# xbeeBoard.net
KiCad netlist of a schematic drawn in EAGLE
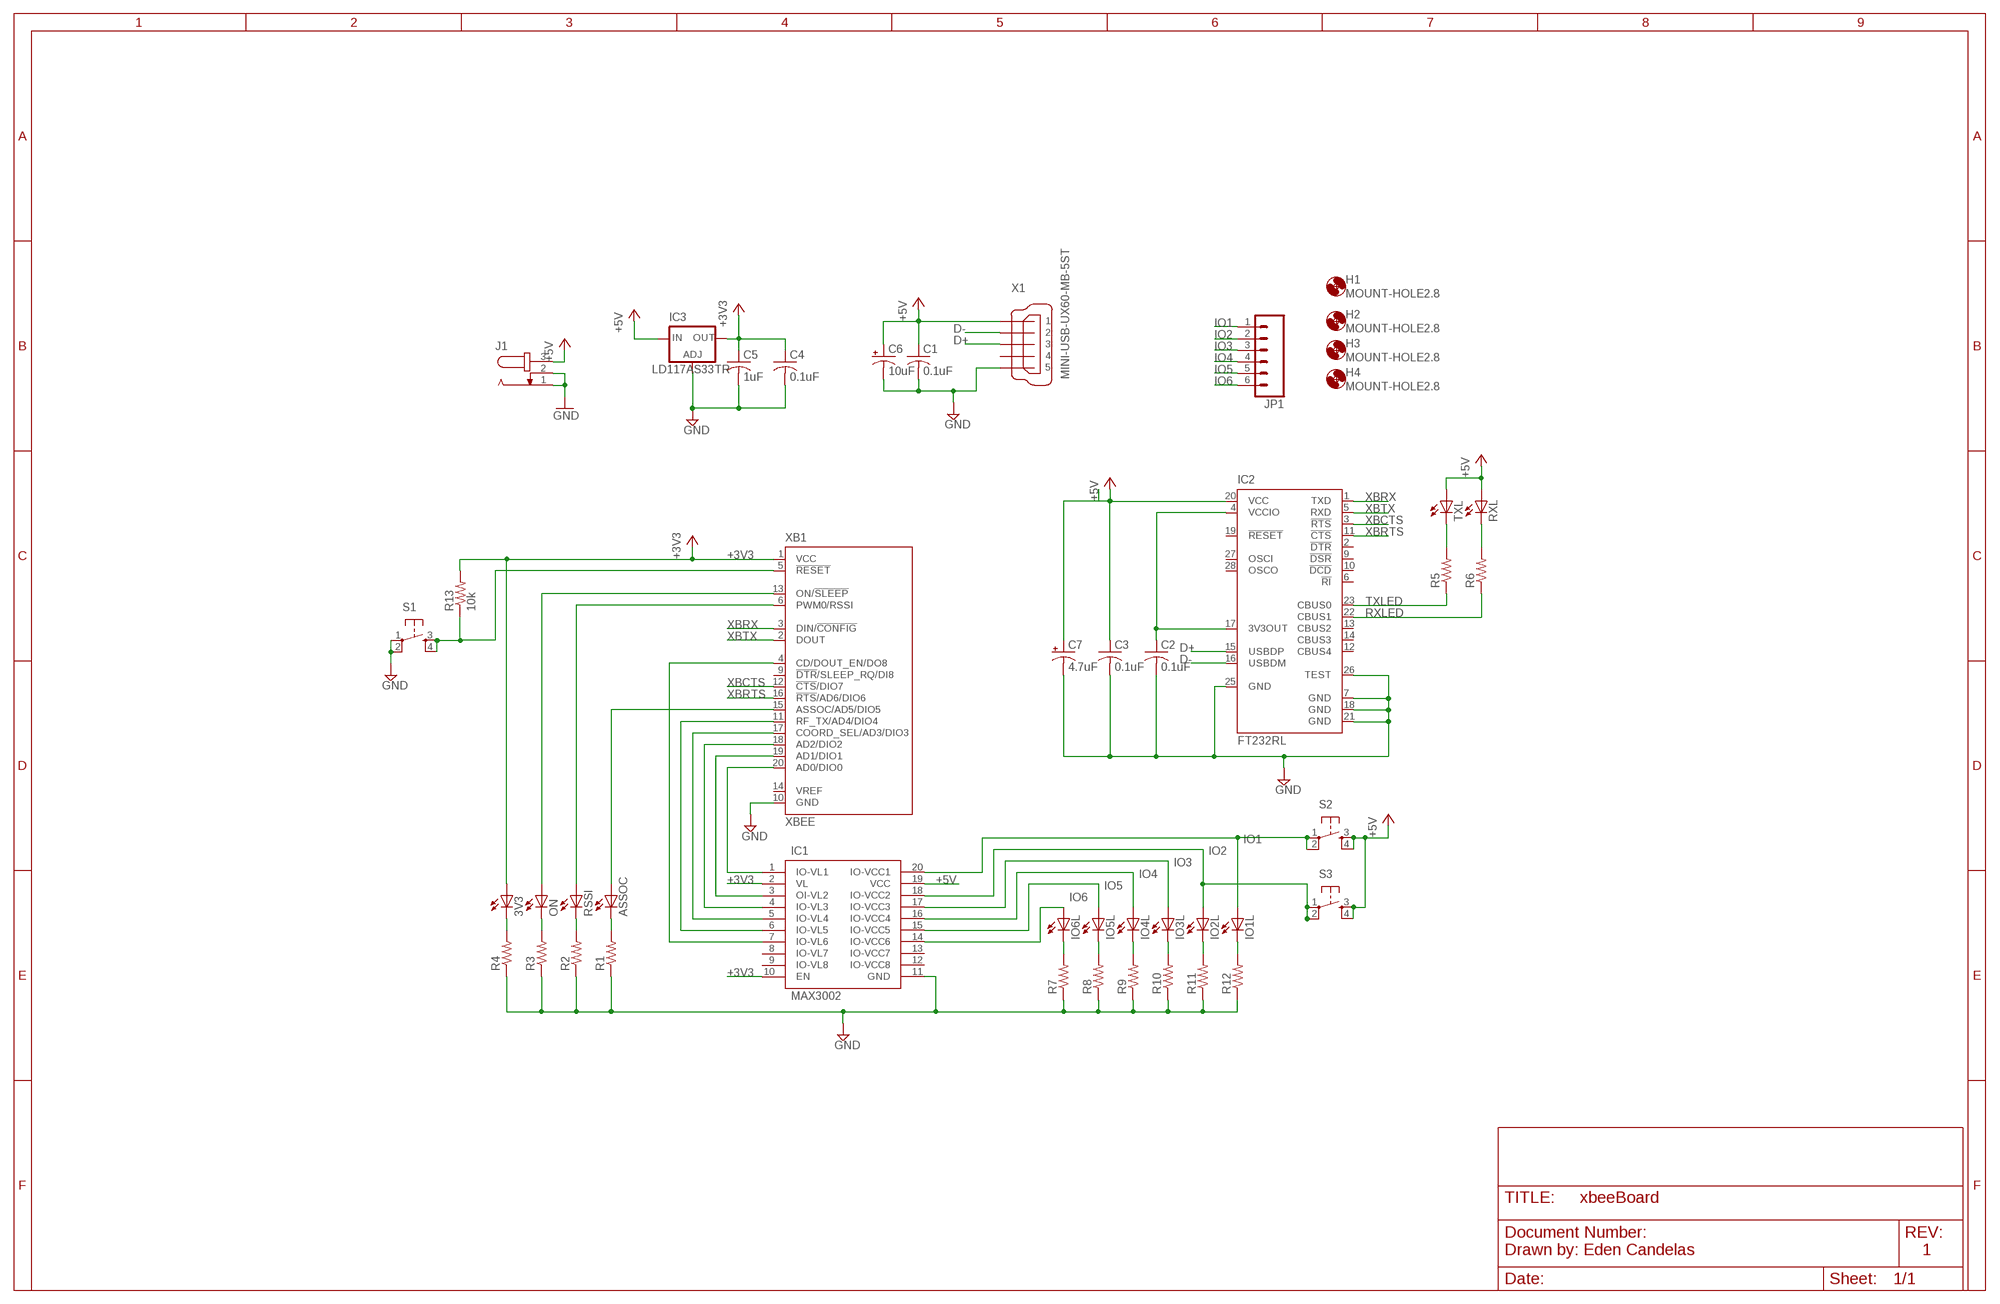
[diagram p0: schematic, sheet 1]

(export (version "E")
  (design (tool "Eeschema 10.0.6"))
  (components
    (comp (ref "3V3")
      (value "LEDCHIPLED_1206")
      (footprint "eagle-import:CHIPLED_1206")
      (libsource (lib "eagle-import") (part "LEDCHIPLED_1206"))
    )
    (comp (ref "ASSOC")
      (value "LEDCHIPLED_1206")
      (footprint "eagle-import:CHIPLED_1206")
      (libsource (lib "eagle-import") (part "LEDCHIPLED_1206"))
    )
    (comp (ref "C1")
      (value "0.1uF")
      (footprint "eagle-import:C1206K")
      (libsource (lib "eagle-import") (part "C-USC1206K"))
    )
    (comp (ref "C2")
      (value "0.1uF")
      (footprint "eagle-import:C1206K")
      (libsource (lib "eagle-import") (part "C-USC1206K"))
    )
    (comp (ref "C3")
      (value "0.1uF")
      (footprint "eagle-import:C1206K")
      (libsource (lib "eagle-import") (part "C-USC1206K"))
    )
    (comp (ref "C4")
      (value "0.1uF")
      (footprint "eagle-import:C1206K")
      (libsource (lib "eagle-import") (part "C-USC1206K"))
    )
    (comp (ref "C5")
      (value "1uF")
      (footprint "eagle-import:C1206K")
      (libsource (lib "eagle-import") (part "C-USC1206K"))
    )
    (comp (ref "C6")
      (value "10uF")
      (footprint "eagle-import:EIA3216")
      (libsource (lib "eagle-import") (part "CAP_POL1206"))
    )
    (comp (ref "C7")
      (value "4.7uF")
      (footprint "eagle-import:EIA3216")
      (libsource (lib "eagle-import") (part "CAP_POL1206"))
    )
    (comp (ref "H1")
      (value "MOUNT-HOLE2.8")
      (footprint "eagle-import:2,8")
      (libsource (lib "eagle-import") (part "MOUNT-HOLE2.8"))
    )
    (comp (ref "H2")
      (value "MOUNT-HOLE2.8")
      (footprint "eagle-import:2,8")
      (libsource (lib "eagle-import") (part "MOUNT-HOLE2.8"))
    )
    (comp (ref "H3")
      (value "MOUNT-HOLE2.8")
      (footprint "eagle-import:2,8")
      (libsource (lib "eagle-import") (part "MOUNT-HOLE2.8"))
    )
    (comp (ref "H4")
      (value "MOUNT-HOLE2.8")
      (footprint "eagle-import:2,8")
      (libsource (lib "eagle-import") (part "MOUNT-HOLE2.8"))
    )
    (comp (ref "IC1")
      (value "MAX3002")
      (footprint "eagle-import:TSSOP-20")
      (libsource (lib "eagle-import") (part "MAX3002"))
    )
    (comp (ref "IC2")
      (value "FT232RL")
      (footprint "eagle-import:SSOP28")
      (libsource (lib "eagle-import") (part "FT232RL"))
    )
    (comp (ref "IC3")
      (value "LD117AS33TR")
      (footprint "eagle-import:SOT223")
      (libsource (lib "eagle-import") (part "LD117A?S33TR"))
    )
    (comp (ref "IO1L")
      (value "LEDCHIPLED_1206")
      (footprint "eagle-import:CHIPLED_1206")
      (libsource (lib "eagle-import") (part "LEDCHIPLED_1206"))
    )
    (comp (ref "IO2L")
      (value "LEDCHIPLED_1206")
      (footprint "eagle-import:CHIPLED_1206")
      (libsource (lib "eagle-import") (part "LEDCHIPLED_1206"))
    )
    (comp (ref "IO3L")
      (value "LEDCHIPLED_1206")
      (footprint "eagle-import:CHIPLED_1206")
      (libsource (lib "eagle-import") (part "LEDCHIPLED_1206"))
    )
    (comp (ref "IO4L")
      (value "LEDCHIPLED_1206")
      (footprint "eagle-import:CHIPLED_1206")
      (libsource (lib "eagle-import") (part "LEDCHIPLED_1206"))
    )
    (comp (ref "IO5L")
      (value "LEDCHIPLED_1206")
      (footprint "eagle-import:CHIPLED_1206")
      (libsource (lib "eagle-import") (part "LEDCHIPLED_1206"))
    )
    (comp (ref "IO6L")
      (value "LEDCHIPLED_1206")
      (footprint "eagle-import:CHIPLED_1206")
      (libsource (lib "eagle-import") (part "LEDCHIPLED_1206"))
    )
    (comp (ref "J1")
      (value "JACK-PLUG0")
      (footprint "eagle-import:SPC4077")
      (libsource (lib "eagle-import") (part "JACK-PLUG0"))
    )
    (comp (ref "JP1")
      (value "M06LONGPADS")
      (footprint "eagle-import:1X06_LONGPADS")
      (libsource (lib "eagle-import") (part "M06LONGPADS"))
    )
    (comp (ref "ON")
      (value "LEDCHIPLED_1206")
      (footprint "eagle-import:CHIPLED_1206")
      (libsource (lib "eagle-import") (part "LEDCHIPLED_1206"))
    )
    (comp (ref "R1")
      (value "R-US_R1206")
      (footprint "eagle-import:R1206")
      (libsource (lib "eagle-import") (part "R-US_R1206"))
    )
    (comp (ref "R2")
      (value "R-US_R1206")
      (footprint "eagle-import:R1206")
      (libsource (lib "eagle-import") (part "R-US_R1206"))
    )
    (comp (ref "R3")
      (value "R-US_R1206")
      (footprint "eagle-import:R1206")
      (libsource (lib "eagle-import") (part "R-US_R1206"))
    )
    (comp (ref "R4")
      (value "R-US_R1206")
      (footprint "eagle-import:R1206")
      (libsource (lib "eagle-import") (part "R-US_R1206"))
    )
    (comp (ref "R5")
      (value "R-US_R1206")
      (footprint "eagle-import:R1206")
      (libsource (lib "eagle-import") (part "R-US_R1206"))
    )
    (comp (ref "R6")
      (value "R-US_R1206")
      (footprint "eagle-import:R1206")
      (libsource (lib "eagle-import") (part "R-US_R1206"))
    )
    (comp (ref "R7")
      (value "R-US_R1206")
      (footprint "eagle-import:R1206")
      (libsource (lib "eagle-import") (part "R-US_R1206"))
    )
    (comp (ref "R8")
      (value "R-US_R1206")
      (footprint "eagle-import:R1206")
      (libsource (lib "eagle-import") (part "R-US_R1206"))
    )
    (comp (ref "R9")
      (value "R-US_R1206")
      (footprint "eagle-import:R1206")
      (libsource (lib "eagle-import") (part "R-US_R1206"))
    )
    (comp (ref "R10")
      (value "R-US_R1206")
      (footprint "eagle-import:R1206")
      (libsource (lib "eagle-import") (part "R-US_R1206"))
    )
    (comp (ref "R11")
      (value "R-US_R1206")
      (footprint "eagle-import:R1206")
      (libsource (lib "eagle-import") (part "R-US_R1206"))
    )
    (comp (ref "R12")
      (value "R-US_R1206")
      (footprint "eagle-import:R1206")
      (libsource (lib "eagle-import") (part "R-US_R1206"))
    )
    (comp (ref "R13")
      (value "10k")
      (footprint "eagle-import:R1206")
      (libsource (lib "eagle-import") (part "R-US_R1206"))
    )
    (comp (ref "RSSI")
      (value "LEDCHIPLED_1206")
      (footprint "eagle-import:CHIPLED_1206")
      (libsource (lib "eagle-import") (part "LEDCHIPLED_1206"))
    )
    (comp (ref "RXL")
      (value "LEDCHIPLED_1206")
      (footprint "eagle-import:CHIPLED_1206")
      (libsource (lib "eagle-import") (part "LEDCHIPLED_1206"))
    )
    (comp (ref "S1")
      (value "TAC_SWITCHPTH")
      (footprint "eagle-import:TACTILE-PTH")
      (libsource (lib "eagle-import") (part "TAC_SWITCHPTH"))
    )
    (comp (ref "S2")
      (value "TAC_SWITCHPTH")
      (footprint "eagle-import:TACTILE-PTH")
      (libsource (lib "eagle-import") (part "TAC_SWITCHPTH"))
    )
    (comp (ref "S3")
      (value "TAC_SWITCHPTH")
      (footprint "eagle-import:TACTILE-PTH")
      (libsource (lib "eagle-import") (part "TAC_SWITCHPTH"))
    )
    (comp (ref "TXL")
      (value "LEDCHIPLED_1206")
      (footprint "eagle-import:CHIPLED_1206")
      (libsource (lib "eagle-import") (part "LEDCHIPLED_1206"))
    )
    (comp (ref "X1")
      (value "MINI-USB-UX60-MB-5ST")
      (footprint "eagle-import:UX60-MB-5ST")
      (libsource (lib "eagle-import") (part "MINI-USB-UX60-MB-5ST"))
    )
    (comp (ref "XB1")
      (value "XBEE")
      (footprint "eagle-import:XBEE")
      (fields (field (name "MPN") "XBP24-Z7UIT-004"))
      (libsource (lib "eagle-import") (part "XBEE"))
    )
  )
  (nets
    (net (code "1") (name "+3V3") (class "Default")
      (node (ref "3V3") (pin "A") (pinfunction "A_A") (pintype "passive"))
      (node (ref "C4") (pin "1") (pinfunction "1_1") (pintype "passive"))
      (node (ref "C5") (pin "1") (pinfunction "1_1") (pintype "passive"))
      (node (ref "IC1") (pin "10") (pinfunction "EN_10") (pintype "input"))
      (node (ref "IC1") (pin "2") (pinfunction "VL_2") (pintype "power_in"))
      (node (ref "IC3") (pin "4") (pinfunction "OUT_4") (pintype "passive"))
      (node (ref "R13") (pin "2") (pinfunction "2_2") (pintype "passive"))
      (node (ref "XB1") (pin "1") (pinfunction "VCC_1") (pintype "power_in"))
    )
    (net (code "2") (name "+5V") (class "Default")
      (node (ref "C1") (pin "1") (pinfunction "1_1") (pintype "passive"))
      (node (ref "C3") (pin "1") (pinfunction "1_1") (pintype "passive"))
      (node (ref "C6") (pin "A") (pinfunction "+_A") (pintype "passive"))
      (node (ref "C7") (pin "A") (pinfunction "+_A") (pintype "passive"))
      (node (ref "IC1") (pin "19") (pinfunction "VCC_19") (pintype "power_in"))
      (node (ref "IC2") (pin "20") (pinfunction "VCC_20") (pintype "power_in"))
      (node (ref "IC3") (pin "3") (pinfunction "IN_3") (pintype "input"))
      (node (ref "J1") (pin "3") (pinfunction "3_3") (pintype "passive"))
      (node (ref "RXL") (pin "A") (pinfunction "A_A") (pintype "passive"))
      (node (ref "S2") (pin "3") (pinfunction "3_3") (pintype "passive"))
      (node (ref "S2") (pin "4") (pinfunction "4_4") (pintype "passive"))
      (node (ref "S3") (pin "3") (pinfunction "3_3") (pintype "passive"))
      (node (ref "S3") (pin "4") (pinfunction "4_4") (pintype "passive"))
      (node (ref "TXL") (pin "A") (pinfunction "A_A") (pintype "passive"))
      (node (ref "X1") (pin "1") (pinfunction "1_1") (pintype "input"))
    )
    (net (code "3") (name "/D+") (class "Default")
      (node (ref "IC2") (pin "15") (pinfunction "USBDP_15") (pintype "bidirectional"))
      (node (ref "X1") (pin "3") (pinfunction "3_3") (pintype "input"))
    )
    (net (code "4") (name "/D-") (class "Default")
      (node (ref "IC2") (pin "16") (pinfunction "USBDM_16") (pintype "bidirectional"))
      (node (ref "X1") (pin "2") (pinfunction "2_2") (pintype "input"))
    )
    (net (code "5") (name "/IO1") (class "Default")
      (node (ref "IC1") (pin "20") (pinfunction "IO-VCC1_20") (pintype "bidirectional"))
      (node (ref "IO1L") (pin "A") (pinfunction "A_A") (pintype "passive"))
      (node (ref "JP1") (pin "1") (pinfunction "1_1") (pintype "passive"))
      (node (ref "S2") (pin "1") (pinfunction "1_1") (pintype "passive"))
      (node (ref "S2") (pin "2") (pinfunction "2_2") (pintype "passive"))
    )
    (net (code "6") (name "/IO2") (class "Default")
      (node (ref "IC1") (pin "18") (pinfunction "IO-VCC2_18") (pintype "bidirectional"))
      (node (ref "IO2L") (pin "A") (pinfunction "A_A") (pintype "passive"))
      (node (ref "JP1") (pin "2") (pinfunction "2_2") (pintype "passive"))
      (node (ref "S3") (pin "1") (pinfunction "1_1") (pintype "passive"))
      (node (ref "S3") (pin "2") (pinfunction "2_2") (pintype "passive"))
    )
    (net (code "7") (name "/IO3") (class "Default")
      (node (ref "IC1") (pin "17") (pinfunction "IO-VCC3_17") (pintype "bidirectional"))
      (node (ref "IO3L") (pin "A") (pinfunction "A_A") (pintype "passive"))
      (node (ref "JP1") (pin "3") (pinfunction "3_3") (pintype "passive"))
    )
    (net (code "8") (name "/IO4") (class "Default")
      (node (ref "IC1") (pin "16") (pinfunction "IO-VCC4_16") (pintype "bidirectional"))
      (node (ref "IO4L") (pin "A") (pinfunction "A_A") (pintype "passive"))
      (node (ref "JP1") (pin "4") (pinfunction "4_4") (pintype "passive"))
    )
    (net (code "9") (name "/IO5") (class "Default")
      (node (ref "IC1") (pin "15") (pinfunction "IO-VCC5_15") (pintype "bidirectional"))
      (node (ref "IO5L") (pin "A") (pinfunction "A_A") (pintype "passive"))
      (node (ref "JP1") (pin "5") (pinfunction "5_5") (pintype "passive"))
    )
    (net (code "10") (name "/IO6") (class "Default")
      (node (ref "IC1") (pin "14") (pinfunction "IO-VCC6_14") (pintype "bidirectional"))
      (node (ref "IO6L") (pin "A") (pinfunction "A_A") (pintype "passive"))
      (node (ref "JP1") (pin "6") (pinfunction "6_6") (pintype "passive"))
    )
    (net (code "11") (name "/RXLED") (class "Default")
      (node (ref "IC2") (pin "22") (pinfunction "CBUS1_22") (pintype "bidirectional"))
      (node (ref "R6") (pin "1") (pinfunction "1_1") (pintype "passive"))
    )
    (net (code "12") (name "/TXLED") (class "Default")
      (node (ref "IC2") (pin "23") (pinfunction "CBUS0_23") (pintype "bidirectional"))
      (node (ref "R5") (pin "1") (pinfunction "1_1") (pintype "passive"))
    )
    (net (code "13") (name "/XBCTS") (class "Default")
      (node (ref "IC2") (pin "3") (pinfunction "~{RTS}_3") (pintype "output"))
      (node (ref "XB1") (pin "12") (pinfunction "~{CTS}/DIO7_12") (pintype "bidirectional"))
    )
    (net (code "14") (name "/XBRTS") (class "Default")
      (node (ref "IC2") (pin "11") (pinfunction "~{CTS}_11") (pintype "input"))
      (node (ref "XB1") (pin "16") (pinfunction "~{RTS}/AD6/DIO6_16") (pintype "bidirectional"))
    )
    (net (code "15") (name "/XBRX") (class "Default")
      (node (ref "IC2") (pin "1") (pinfunction "TXD_1") (pintype "output"))
      (node (ref "XB1") (pin "3") (pinfunction "DIN/~{CONFIG}_3") (pintype "input"))
    )
    (net (code "16") (name "/XBTX") (class "Default")
      (node (ref "IC2") (pin "5") (pinfunction "RXD_5") (pintype "input"))
      (node (ref "XB1") (pin "2") (pinfunction "DOUT_2") (pintype "output"))
    )
    (net (code "17") (name "GND") (class "Default")
      (node (ref "C1") (pin "2") (pinfunction "2_2") (pintype "passive"))
      (node (ref "C2") (pin "2") (pinfunction "2_2") (pintype "passive"))
      (node (ref "C3") (pin "2") (pinfunction "2_2") (pintype "passive"))
      (node (ref "C4") (pin "2") (pinfunction "2_2") (pintype "passive"))
      (node (ref "C5") (pin "2") (pinfunction "2_2") (pintype "passive"))
      (node (ref "C6") (pin "C") (pinfunction "-_C") (pintype "passive"))
      (node (ref "C7") (pin "C") (pinfunction "-_C") (pintype "passive"))
      (node (ref "IC1") (pin "11") (pinfunction "GND_11") (pintype "power_in"))
      (node (ref "IC2") (pin "18") (pinfunction "GND_18") (pintype "power_in"))
      (node (ref "IC2") (pin "21") (pinfunction "GND_21") (pintype "power_in"))
      (node (ref "IC2") (pin "25") (pinfunction "GND_25") (pintype "power_in"))
      (node (ref "IC2") (pin "26") (pinfunction "TEST_26") (pintype "input"))
      (node (ref "IC2") (pin "7") (pinfunction "GND_7") (pintype "power_in"))
      (node (ref "IC3") (pin "1") (pinfunction "ADJ_1") (pintype "input"))
      (node (ref "J1") (pin "1") (pinfunction "1_1") (pintype "passive"))
      (node (ref "J1") (pin "2") (pinfunction "2_2") (pintype "passive"))
      (node (ref "R1") (pin "1") (pinfunction "1_1") (pintype "passive"))
      (node (ref "R10") (pin "1") (pinfunction "1_1") (pintype "passive"))
      (node (ref "R11") (pin "1") (pinfunction "1_1") (pintype "passive"))
      (node (ref "R12") (pin "1") (pinfunction "1_1") (pintype "passive"))
      (node (ref "R2") (pin "1") (pinfunction "1_1") (pintype "passive"))
      (node (ref "R3") (pin "1") (pinfunction "1_1") (pintype "passive"))
      (node (ref "R4") (pin "1") (pinfunction "1_1") (pintype "passive"))
      (node (ref "R7") (pin "1") (pinfunction "1_1") (pintype "passive"))
      (node (ref "R8") (pin "1") (pinfunction "1_1") (pintype "passive"))
      (node (ref "R9") (pin "1") (pinfunction "1_1") (pintype "passive"))
      (node (ref "S1") (pin "1") (pinfunction "1_1") (pintype "passive"))
      (node (ref "S1") (pin "2") (pinfunction "2_2") (pintype "passive"))
      (node (ref "X1") (pin "5") (pinfunction "5_5") (pintype "input"))
      (node (ref "XB1") (pin "10") (pinfunction "GND_10") (pintype "power_in"))
    )
    (net (code "18") (name "Net-(3V3-PadC)") (class "Default")
      (node (ref "3V3") (pin "C") (pinfunction "C_C") (pintype "passive"))
      (node (ref "R4") (pin "2") (pinfunction "2_2") (pintype "passive"))
    )
    (net (code "19") (name "Net-(ASSOC-PadC)") (class "Default")
      (node (ref "ASSOC") (pin "C") (pinfunction "C_C") (pintype "passive"))
      (node (ref "R1") (pin "2") (pinfunction "2_2") (pintype "passive"))
    )
    (net (code "20") (name "Net-(IC1-IO-VL1)") (class "Default")
      (node (ref "IC1") (pin "1") (pinfunction "IO-VL1_1") (pintype "bidirectional"))
      (node (ref "XB1") (pin "20") (pinfunction "AD0/DIO0_20") (pintype "bidirectional"))
    )
    (net (code "21") (name "Net-(IC1-IO-VL3)") (class "Default")
      (node (ref "IC1") (pin "4") (pinfunction "IO-VL3_4") (pintype "bidirectional"))
      (node (ref "XB1") (pin "18") (pinfunction "AD2/DIO2_18") (pintype "bidirectional"))
    )
    (net (code "22") (name "Net-(IC1-IO-VL4)") (class "Default")
      (node (ref "IC1") (pin "5") (pinfunction "IO-VL4_5") (pintype "bidirectional"))
      (node (ref "XB1") (pin "17") (pinfunction "COORD_SEL/AD3/DIO3_17") (pintype "bidirectional"))
    )
    (net (code "23") (name "Net-(IC1-IO-VL5)") (class "Default")
      (node (ref "IC1") (pin "6") (pinfunction "IO-VL5_6") (pintype "bidirectional"))
      (node (ref "XB1") (pin "11") (pinfunction "RF_TX/AD4/DIO4_11") (pintype "bidirectional"))
    )
    (net (code "24") (name "Net-(IC1-IO-VL6)") (class "Default")
      (node (ref "IC1") (pin "7") (pinfunction "IO-VL6_7") (pintype "bidirectional"))
      (node (ref "XB1") (pin "4") (pinfunction "CD/DOUT_EN/DO8_4") (pintype "output"))
    )
    (net (code "25") (name "Net-(IC1-OI-VL2)") (class "Default")
      (node (ref "IC1") (pin "3") (pinfunction "OI-VL2_3") (pintype "bidirectional"))
      (node (ref "XB1") (pin "19") (pinfunction "AD1/DIO1_19") (pintype "bidirectional"))
    )
    (net (code "26") (name "Net-(IC2-3V3OUT)") (class "Default")
      (node (ref "C2") (pin "1") (pinfunction "1_1") (pintype "passive"))
      (node (ref "IC2") (pin "17") (pinfunction "3V3OUT_17") (pintype "output"))
      (node (ref "IC2") (pin "4") (pinfunction "VCCIO_4") (pintype "power_in"))
    )
    (net (code "27") (name "Net-(IO1L-PadC)") (class "Default")
      (node (ref "IO1L") (pin "C") (pinfunction "C_C") (pintype "passive"))
      (node (ref "R12") (pin "2") (pinfunction "2_2") (pintype "passive"))
    )
    (net (code "28") (name "Net-(IO2L-PadC)") (class "Default")
      (node (ref "IO2L") (pin "C") (pinfunction "C_C") (pintype "passive"))
      (node (ref "R11") (pin "2") (pinfunction "2_2") (pintype "passive"))
    )
    (net (code "29") (name "Net-(IO3L-PadC)") (class "Default")
      (node (ref "IO3L") (pin "C") (pinfunction "C_C") (pintype "passive"))
      (node (ref "R10") (pin "2") (pinfunction "2_2") (pintype "passive"))
    )
    (net (code "30") (name "Net-(IO4L-PadC)") (class "Default")
      (node (ref "IO4L") (pin "C") (pinfunction "C_C") (pintype "passive"))
      (node (ref "R9") (pin "2") (pinfunction "2_2") (pintype "passive"))
    )
    (net (code "31") (name "Net-(IO5L-PadC)") (class "Default")
      (node (ref "IO5L") (pin "C") (pinfunction "C_C") (pintype "passive"))
      (node (ref "R8") (pin "2") (pinfunction "2_2") (pintype "passive"))
    )
    (net (code "32") (name "Net-(IO6L-PadC)") (class "Default")
      (node (ref "IO6L") (pin "C") (pinfunction "C_C") (pintype "passive"))
      (node (ref "R7") (pin "2") (pinfunction "2_2") (pintype "passive"))
    )
    (net (code "33") (name "Net-(ON-PadC)") (class "Default")
      (node (ref "ON") (pin "C") (pinfunction "C_C") (pintype "passive"))
      (node (ref "R3") (pin "2") (pinfunction "2_2") (pintype "passive"))
    )
    (net (code "34") (name "Net-(R2-Pad2)") (class "Default")
      (node (ref "R2") (pin "2") (pinfunction "2_2") (pintype "passive"))
      (node (ref "RSSI") (pin "C") (pinfunction "C_C") (pintype "passive"))
    )
    (net (code "35") (name "Net-(R5-Pad2)") (class "Default")
      (node (ref "R5") (pin "2") (pinfunction "2_2") (pintype "passive"))
      (node (ref "TXL") (pin "C") (pinfunction "C_C") (pintype "passive"))
    )
    (net (code "36") (name "Net-(R6-Pad2)") (class "Default")
      (node (ref "R6") (pin "2") (pinfunction "2_2") (pintype "passive"))
      (node (ref "RXL") (pin "C") (pinfunction "C_C") (pintype "passive"))
    )
    (net (code "37") (name "Net-(XB1-ASSOC{slash}AD5{slash}DIO5)") (class "Default")
      (node (ref "ASSOC") (pin "A") (pinfunction "A_A") (pintype "passive"))
      (node (ref "XB1") (pin "15") (pinfunction "ASSOC/AD5/DIO5_15") (pintype "bidirectional"))
    )
    (net (code "38") (name "Net-(XB1-ON{slash}~{SLEEP})") (class "Default")
      (node (ref "ON") (pin "A") (pinfunction "A_A") (pintype "passive"))
      (node (ref "XB1") (pin "13") (pinfunction "ON/~{SLEEP}_13") (pintype "output"))
    )
    (net (code "39") (name "Net-(XB1-PWM0{slash}RSSI)") (class "Default")
      (node (ref "RSSI") (pin "A") (pinfunction "A_A") (pintype "passive"))
      (node (ref "XB1") (pin "6") (pinfunction "PWM0/RSSI_6") (pintype "output"))
    )
    (net (code "40") (name "Net-(XB1-~{RESET})") (class "Default")
      (node (ref "R13") (pin "1") (pinfunction "1_1") (pintype "passive"))
      (node (ref "S1") (pin "3") (pinfunction "3_3") (pintype "passive"))
      (node (ref "S1") (pin "4") (pinfunction "4_4") (pintype "passive"))
      (node (ref "XB1") (pin "5") (pinfunction "~{RESET}_5") (pintype "input"))
    )
    (net (code "41") (name "unconnected-(IC1-IO-VCC7-Pad13)") (class "Default")
      (node (ref "IC1") (pin "13") (pinfunction "IO-VCC7_13") (pintype "bidirectional"))
    )
    (net (code "42") (name "unconnected-(IC1-IO-VCC8-Pad12)") (class "Default")
      (node (ref "IC1") (pin "12") (pinfunction "IO-VCC8_12") (pintype "bidirectional"))
    )
    (net (code "43") (name "unconnected-(IC1-IO-VL7-Pad8)") (class "Default")
      (node (ref "IC1") (pin "8") (pinfunction "IO-VL7_8") (pintype "bidirectional"))
    )
    (net (code "44") (name "unconnected-(IC1-IO-VL8-Pad9)") (class "Default")
      (node (ref "IC1") (pin "9") (pinfunction "IO-VL8_9") (pintype "bidirectional"))
    )
    (net (code "45") (name "unconnected-(IC2-CBUS2-Pad13)") (class "Default")
      (node (ref "IC2") (pin "13") (pinfunction "CBUS2_13") (pintype "bidirectional"))
    )
    (net (code "46") (name "unconnected-(IC2-CBUS3-Pad14)") (class "Default")
      (node (ref "IC2") (pin "14") (pinfunction "CBUS3_14") (pintype "bidirectional"))
    )
    (net (code "47") (name "unconnected-(IC2-CBUS4-Pad12)") (class "Default")
      (node (ref "IC2") (pin "12") (pinfunction "CBUS4_12") (pintype "bidirectional"))
    )
    (net (code "48") (name "unconnected-(IC2-OSCI-Pad27)") (class "Default")
      (node (ref "IC2") (pin "27") (pinfunction "OSCI_27") (pintype "input"))
    )
    (net (code "49") (name "unconnected-(IC2-OSCO-Pad28)") (class "Default")
      (node (ref "IC2") (pin "28") (pinfunction "OSCO_28") (pintype "output"))
    )
    (net (code "50") (name "unconnected-(IC2-~{DCD}-Pad10)") (class "Default")
      (node (ref "IC2") (pin "10") (pinfunction "~{DCD}_10") (pintype "input"))
    )
    (net (code "51") (name "unconnected-(IC2-~{DSR}-Pad9)") (class "Default")
      (node (ref "IC2") (pin "9") (pinfunction "~{DSR}_9") (pintype "input"))
    )
    (net (code "52") (name "unconnected-(IC2-~{DTR}-Pad2)") (class "Default")
      (node (ref "IC2") (pin "2") (pinfunction "~{DTR}_2") (pintype "output"))
    )
    (net (code "53") (name "unconnected-(IC2-~{RESET}-Pad19)") (class "Default")
      (node (ref "IC2") (pin "19") (pinfunction "~{RESET}_19") (pintype "input"))
    )
    (net (code "54") (name "unconnected-(IC2-~{RI}-Pad6)") (class "Default")
      (node (ref "IC2") (pin "6") (pinfunction "~{RI}_6") (pintype "input"))
    )
    (net (code "55") (name "unconnected-(X1-Pad4)") (class "Default")
      (node (ref "X1") (pin "4") (pinfunction "4_4") (pintype "input"))
    )
    (net (code "56") (name "unconnected-(XB1-VREF-Pad14)") (class "Default")
      (node (ref "XB1") (pin "14") (pinfunction "VREF_14") (pintype "input"))
    )
    (net (code "57") (name "unconnected-(XB1-~{DTR}{slash}SLEEP_RQ{slash}DI8-Pad9)") (class "Default")
      (node (ref "XB1") (pin "9") (pinfunction "~{DTR}/SLEEP_RQ/DI8_9") (pintype "bidirectional"))
    )
  )
)
